# CAN.net
KiCad netlist of a schematic drawn in Altium Designer
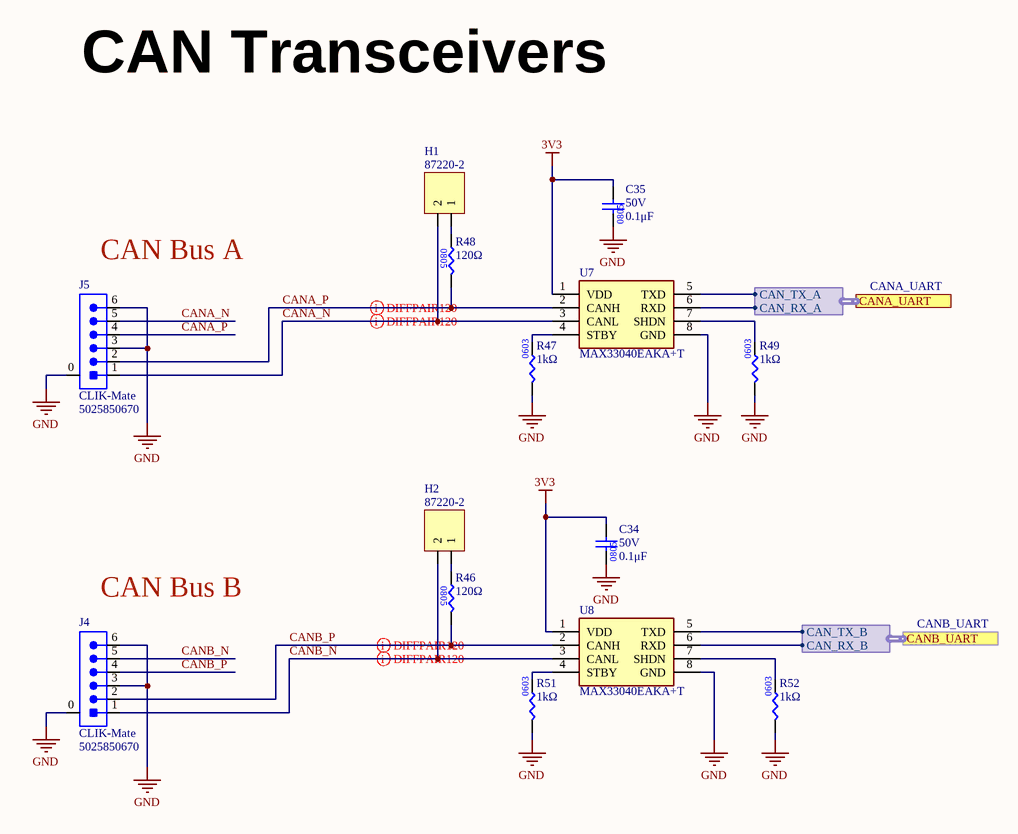
[diagram p0: CAN.SchDoc]

(export (version "E")
  (design (tool "Eeschema 10.0.6"))
  (components
    (comp (ref "C34")
      (value "0.1μF")
      (footprint "CAP2012")
      (description "CAP CER 0.1UF 50V X7R 0805")
      (fields
        (field (name "VOLTAGE RATING") "50V")
        (field (name "LCSC PART #") "C49678")
        (field (name "Comment") "CAP_0.1uF_50V_0805")
      )
      (libsource (lib "UWRT_Schematic_Library_2020") (part "CAP_0.1uF_50V_0805"))
    )
    (comp (ref "C35")
      (value "0.1μF")
      (footprint "CAP2012")
      (description "CAP CER 0.1UF 50V X7R 0805")
      (fields
        (field (name "VOLTAGE RATING") "50V")
        (field (name "LCSC PART #") "C49678")
        (field (name "Comment") "CAP_0.1uF_50V_0805")
      )
      (libsource (lib "UWRT_Schematic_Library_2020") (part "CAP_0.1uF_50V_0805"))
    )
    (comp (ref "H1")
      (value "JUMPER_2")
      (footprint "HDR1X2")
      (description "HEADER 2X1")
      (fields (field (name "MANUFACTURER PART NUMBER 1") "87220-2"))
      (libsource (lib "UWRT_Schematic_Library_2020") (part "JUMPER_2"))
    )
    (comp (ref "H2")
      (value "JUMPER_2")
      (footprint "HDR1X2")
      (description "HEADER 2X1")
      (fields (field (name "MANUFACTURER PART NUMBER 1") "87220-2"))
      (libsource (lib "UWRT_Schematic_Library_2020") (part "JUMPER_2"))
    )
    (comp (ref "J4")
      (value "CON_6M_SM_RA_1.5mm")
      (footprint "MOLEX-5025850670")
      (description "CONN HEADER SMD RIGHT ANGLE 1.5 MM PITCH")
      (fields (field (name "FAMILY") "CLIK-Mate") (field (name "MANUFACTURER PART NUMBER 1") "5025850670"))
      (libsource (lib "UWRT_Schematic_Library_2020") (part "CON_6M_SM_RA_1.5mm"))
    )
    (comp (ref "J5")
      (value "CON_6M_SM_RA_1.5mm")
      (footprint "MOLEX-5025850670")
      (description "CONN HEADER SMD RIGHT ANGLE 1.5 MM PITCH")
      (fields (field (name "FAMILY") "CLIK-Mate") (field (name "MANUFACTURER PART NUMBER 1") "5025850670"))
      (libsource (lib "UWRT_Schematic_Library_2020") (part "CON_6M_SM_RA_1.5mm"))
    )
    (comp (ref "R46")
      (value "120Ω")
      (footprint "RES0805")
      (description "RES 120 OHM 1% 1/8W 0805")
      (fields (field (name "LCSC PART #") "C17437") (field (name "Comment") "RES_120Ω_0805_1%"))
      (libsource (lib "UWRT_Schematic_Library_2020") (part "RES_120Ω_0805_1%"))
    )
    (comp (ref "R47")
      (value "1kΩ")
      (footprint "RES0603")
      (description "RES 1K OHM 5% 1/10W 0603")
      (fields (field (name "Comment") "RES_1kΩ_0603_5%"))
      (libsource (lib "UWRT_Schematic_Library_2020") (part "RES_1kΩ_0603_5%"))
    )
    (comp (ref "R48")
      (value "120Ω")
      (footprint "RES0805")
      (description "RES 120 OHM 1% 1/8W 0805")
      (fields (field (name "LCSC PART #") "C17437") (field (name "Comment") "RES_120Ω_0805_1%"))
      (libsource (lib "UWRT_Schematic_Library_2020") (part "RES_120Ω_0805_1%"))
    )
    (comp (ref "R49")
      (value "1kΩ")
      (footprint "RES0603")
      (description "RES 1K OHM 5% 1/10W 0603")
      (fields (field (name "Comment") "RES_1kΩ_0603_5%"))
      (libsource (lib "UWRT_Schematic_Library_2020") (part "RES_1kΩ_0603_5%"))
    )
    (comp (ref "R51")
      (value "1kΩ")
      (footprint "RES0603")
      (description "RES 1K OHM 5% 1/10W 0603")
      (fields (field (name "Comment") "RES_1kΩ_0603_5%"))
      (libsource (lib "UWRT_Schematic_Library_2020") (part "RES_1kΩ_0603_5%"))
    )
    (comp (ref "R52")
      (value "1kΩ")
      (footprint "RES0603")
      (description "RES 1K OHM 5% 1/10W 0603")
      (fields (field (name "Comment") "RES_1kΩ_0603_5%"))
      (libsource (lib "UWRT_Schematic_Library_2020") (part "RES_1kΩ_0603_5%"))
    )
    (comp (ref "U7")
      (value "MAX33040EAKA+T")
      (footprint "SOT65P280X145-8N")
      (description "Integrated Circuit")
      (fields (field (name "MOUSER PART NUMBER") "700-MAX33040EAKA+T"))
      (libsource (lib "UWRT_Schematic_Library_2020") (part "MAX33040EAKA+T"))
    )
    (comp (ref "U8")
      (value "MAX33040EAKA+T")
      (footprint "SOT65P280X145-8N")
      (description "Integrated Circuit")
      (fields (field (name "MOUSER PART NUMBER") "700-MAX33040EAKA+T"))
      (libsource (lib "UWRT_Schematic_Library_2020") (part "MAX33040EAKA+T"))
    )
  )
  (nets
    (net (code "3") (name "/CANA_N") (class "Default")
      (node (ref "H1") (pin "2") (pinfunction "2_2") (pintype "passive"))
      (node (ref "J5") (pin "1") (pinfunction "1_1") (pintype "passive"))
      (node (ref "J5") (pin "5") (pinfunction "5_5") (pintype "passive"))
      (node (ref "U7") (pin "3") (pinfunction "CANL_3") (pintype "passive"))
    )
    (net (code "4") (name "/CANA_P") (class "Default")
      (node (ref "J5") (pin "2") (pinfunction "2_2") (pintype "passive"))
      (node (ref "J5") (pin "4") (pinfunction "4_4") (pintype "passive"))
      (node (ref "R48") (pin "2") (pinfunction "2_2") (pintype "passive"))
      (node (ref "U7") (pin "2") (pinfunction "CANH_2") (pintype "passive"))
    )
    (net (code "5") (name "/CANB_N") (class "Default")
      (node (ref "H2") (pin "2") (pinfunction "2_2") (pintype "passive"))
      (node (ref "J4") (pin "1") (pinfunction "1_1") (pintype "passive"))
      (node (ref "J4") (pin "5") (pinfunction "5_5") (pintype "passive"))
      (node (ref "U8") (pin "3") (pinfunction "CANL_3") (pintype "passive"))
    )
    (net (code "6") (name "/CANB_P") (class "Default")
      (node (ref "J4") (pin "2") (pinfunction "2_2") (pintype "passive"))
      (node (ref "J4") (pin "4") (pinfunction "4_4") (pintype "passive"))
      (node (ref "R46") (pin "2") (pinfunction "2_2") (pintype "passive"))
      (node (ref "U8") (pin "2") (pinfunction "CANH_2") (pintype "passive"))
    )
    (net (code "7") (name "/CAN_RX_A") (class "Default")
      (node (ref "U7") (pin "6") (pinfunction "RXD_6") (pintype "passive"))
    )
    (net (code "8") (name "/CAN_RX_B") (class "Default")
      (node (ref "U8") (pin "6") (pinfunction "RXD_6") (pintype "passive"))
    )
    (net (code "9") (name "/CAN_TX_A") (class "Default")
      (node (ref "U7") (pin "5") (pinfunction "TXD_5") (pintype "passive"))
    )
    (net (code "10") (name "/CAN_TX_B") (class "Default")
      (node (ref "U8") (pin "5") (pinfunction "TXD_5") (pintype "passive"))
    )
    (net (code "13") (name "3V3") (class "Default")
      (node (ref "C34") (pin "2") (pinfunction "2_2") (pintype "passive"))
      (node (ref "C35") (pin "2") (pinfunction "2_2") (pintype "passive"))
      (node (ref "U7") (pin "1") (pinfunction "VDD_1") (pintype "passive"))
      (node (ref "U8") (pin "1") (pinfunction "VDD_1") (pintype "passive"))
    )
    (net (code "14") (name "GND") (class "Default")
      (node (ref "C34") (pin "1") (pinfunction "1_1") (pintype "passive"))
      (node (ref "C35") (pin "1") (pinfunction "1_1") (pintype "passive"))
      (node (ref "J4") (pin "0") (pinfunction "0_0") (pintype "passive"))
      (node (ref "J4") (pin "3") (pinfunction "3_3") (pintype "passive"))
      (node (ref "J4") (pin "6") (pinfunction "6_6") (pintype "passive"))
      (node (ref "J5") (pin "0") (pinfunction "0_0") (pintype "passive"))
      (node (ref "J5") (pin "3") (pinfunction "3_3") (pintype "passive"))
      (node (ref "J5") (pin "6") (pinfunction "6_6") (pintype "passive"))
      (node (ref "R47") (pin "1") (pinfunction "1_1") (pintype "passive"))
      (node (ref "R49") (pin "1") (pinfunction "1_1") (pintype "passive"))
      (node (ref "R51") (pin "1") (pinfunction "1_1") (pintype "passive"))
      (node (ref "R52") (pin "1") (pinfunction "1_1") (pintype "passive"))
      (node (ref "U7") (pin "8") (pinfunction "GND_8") (pintype "passive"))
      (node (ref "U8") (pin "8") (pinfunction "GND_8") (pintype "passive"))
    )
    (net (code "15") (name "Net-(H1-Pad1)") (class "Default")
      (node (ref "H1") (pin "1") (pinfunction "1_1") (pintype "passive"))
      (node (ref "R48") (pin "1") (pinfunction "1_1") (pintype "passive"))
    )
    (net (code "16") (name "Net-(H2-Pad1)") (class "Default")
      (node (ref "H2") (pin "1") (pinfunction "1_1") (pintype "passive"))
      (node (ref "R46") (pin "1") (pinfunction "1_1") (pintype "passive"))
    )
    (net (code "17") (name "Net-(U7-SHDN)") (class "Default")
      (node (ref "R49") (pin "2") (pinfunction "2_2") (pintype "passive"))
      (node (ref "U7") (pin "7") (pinfunction "SHDN_7") (pintype "passive"))
    )
    (net (code "18") (name "Net-(U7-STBY)") (class "Default")
      (node (ref "R47") (pin "2") (pinfunction "2_2") (pintype "passive"))
      (node (ref "U7") (pin "4") (pinfunction "STBY_4") (pintype "passive"))
    )
    (net (code "19") (name "Net-(U8-SHDN)") (class "Default")
      (node (ref "R52") (pin "2") (pinfunction "2_2") (pintype "passive"))
      (node (ref "U8") (pin "7") (pinfunction "SHDN_7") (pintype "passive"))
    )
    (net (code "20") (name "Net-(U8-STBY)") (class "Default")
      (node (ref "R51") (pin "2") (pinfunction "2_2") (pintype "passive"))
      (node (ref "U8") (pin "4") (pinfunction "STBY_4") (pintype "passive"))
    )
  )
)
